# marquee-neopixel.net
KiCad netlist of a schematic drawn in EAGLE
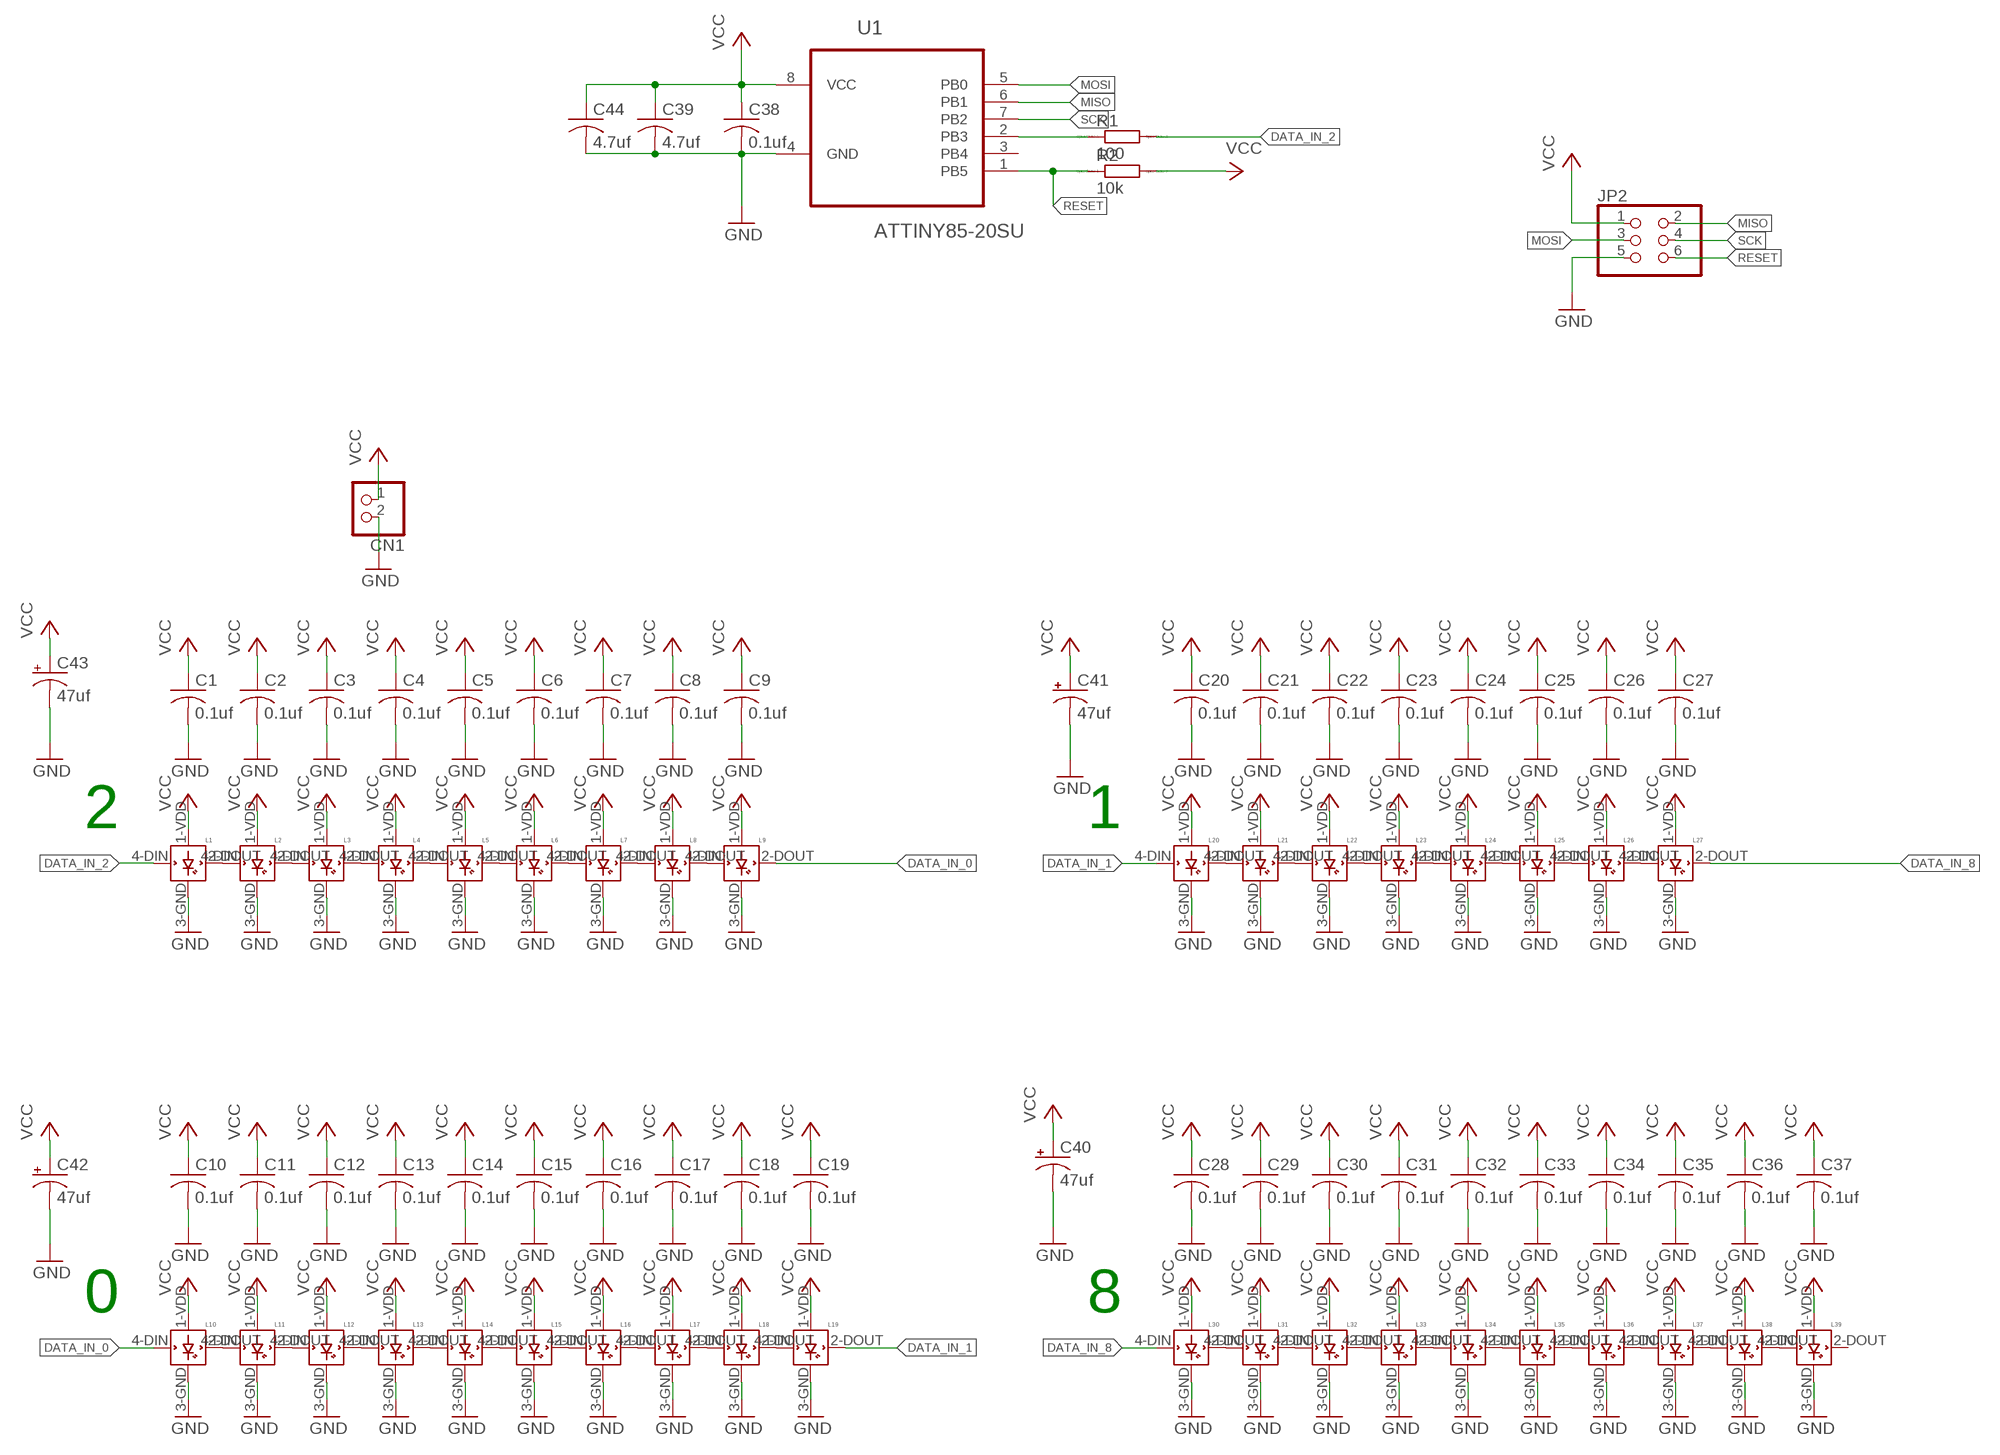
[diagram p0: schematic, sheet 1]

(export (version "E")
  (design (tool "Eeschema 10.0.6"))
  (components
    (comp (ref "C1")
      (value "0.1uf")
      (footprint "eagle-import:C0603")
      (libsource (lib "eagle-import") (part "C-USC0603"))
    )
    (comp (ref "C2")
      (value "0.1uf")
      (footprint "eagle-import:C0603")
      (libsource (lib "eagle-import") (part "C-USC0603"))
    )
    (comp (ref "C3")
      (value "0.1uf")
      (footprint "eagle-import:C0603")
      (libsource (lib "eagle-import") (part "C-USC0603"))
    )
    (comp (ref "C4")
      (value "0.1uf")
      (footprint "eagle-import:C0603")
      (libsource (lib "eagle-import") (part "C-USC0603"))
    )
    (comp (ref "C5")
      (value "0.1uf")
      (footprint "eagle-import:C0603")
      (libsource (lib "eagle-import") (part "C-USC0603"))
    )
    (comp (ref "C6")
      (value "0.1uf")
      (footprint "eagle-import:C0603")
      (libsource (lib "eagle-import") (part "C-USC0603"))
    )
    (comp (ref "C7")
      (value "0.1uf")
      (footprint "eagle-import:C0603")
      (libsource (lib "eagle-import") (part "C-USC0603"))
    )
    (comp (ref "C8")
      (value "0.1uf")
      (footprint "eagle-import:C0603")
      (libsource (lib "eagle-import") (part "C-USC0603"))
    )
    (comp (ref "C9")
      (value "0.1uf")
      (footprint "eagle-import:C0603")
      (libsource (lib "eagle-import") (part "C-USC0603"))
    )
    (comp (ref "C10")
      (value "0.1uf")
      (footprint "eagle-import:C0603")
      (libsource (lib "eagle-import") (part "C-USC0603"))
    )
    (comp (ref "C11")
      (value "0.1uf")
      (footprint "eagle-import:C0603")
      (libsource (lib "eagle-import") (part "C-USC0603"))
    )
    (comp (ref "C12")
      (value "0.1uf")
      (footprint "eagle-import:C0603")
      (libsource (lib "eagle-import") (part "C-USC0603"))
    )
    (comp (ref "C13")
      (value "0.1uf")
      (footprint "eagle-import:C0603")
      (libsource (lib "eagle-import") (part "C-USC0603"))
    )
    (comp (ref "C14")
      (value "0.1uf")
      (footprint "eagle-import:C0603")
      (libsource (lib "eagle-import") (part "C-USC0603"))
    )
    (comp (ref "C15")
      (value "0.1uf")
      (footprint "eagle-import:C0603")
      (libsource (lib "eagle-import") (part "C-USC0603"))
    )
    (comp (ref "C16")
      (value "0.1uf")
      (footprint "eagle-import:C0603")
      (libsource (lib "eagle-import") (part "C-USC0603"))
    )
    (comp (ref "C17")
      (value "0.1uf")
      (footprint "eagle-import:C0603")
      (libsource (lib "eagle-import") (part "C-USC0603"))
    )
    (comp (ref "C18")
      (value "0.1uf")
      (footprint "eagle-import:C0603")
      (libsource (lib "eagle-import") (part "C-USC0603"))
    )
    (comp (ref "C19")
      (value "0.1uf")
      (footprint "eagle-import:C0603")
      (libsource (lib "eagle-import") (part "C-USC0603"))
    )
    (comp (ref "C20")
      (value "0.1uf")
      (footprint "eagle-import:C0603")
      (libsource (lib "eagle-import") (part "C-USC0603"))
    )
    (comp (ref "C21")
      (value "0.1uf")
      (footprint "eagle-import:C0603")
      (libsource (lib "eagle-import") (part "C-USC0603"))
    )
    (comp (ref "C22")
      (value "0.1uf")
      (footprint "eagle-import:C0603")
      (libsource (lib "eagle-import") (part "C-USC0603"))
    )
    (comp (ref "C23")
      (value "0.1uf")
      (footprint "eagle-import:C0603")
      (libsource (lib "eagle-import") (part "C-USC0603"))
    )
    (comp (ref "C24")
      (value "0.1uf")
      (footprint "eagle-import:C0603")
      (libsource (lib "eagle-import") (part "C-USC0603"))
    )
    (comp (ref "C25")
      (value "0.1uf")
      (footprint "eagle-import:C0603")
      (libsource (lib "eagle-import") (part "C-USC0603"))
    )
    (comp (ref "C26")
      (value "0.1uf")
      (footprint "eagle-import:C0603")
      (libsource (lib "eagle-import") (part "C-USC0603"))
    )
    (comp (ref "C27")
      (value "0.1uf")
      (footprint "eagle-import:C0603")
      (libsource (lib "eagle-import") (part "C-USC0603"))
    )
    (comp (ref "C28")
      (value "0.1uf")
      (footprint "eagle-import:C0603")
      (libsource (lib "eagle-import") (part "C-USC0603"))
    )
    (comp (ref "C29")
      (value "0.1uf")
      (footprint "eagle-import:C0603")
      (libsource (lib "eagle-import") (part "C-USC0603"))
    )
    (comp (ref "C30")
      (value "0.1uf")
      (footprint "eagle-import:C0603")
      (libsource (lib "eagle-import") (part "C-USC0603"))
    )
    (comp (ref "C31")
      (value "0.1uf")
      (footprint "eagle-import:C0603")
      (libsource (lib "eagle-import") (part "C-USC0603"))
    )
    (comp (ref "C32")
      (value "0.1uf")
      (footprint "eagle-import:C0603")
      (libsource (lib "eagle-import") (part "C-USC0603"))
    )
    (comp (ref "C33")
      (value "0.1uf")
      (footprint "eagle-import:C0603")
      (libsource (lib "eagle-import") (part "C-USC0603"))
    )
    (comp (ref "C34")
      (value "0.1uf")
      (footprint "eagle-import:C0603")
      (libsource (lib "eagle-import") (part "C-USC0603"))
    )
    (comp (ref "C35")
      (value "0.1uf")
      (footprint "eagle-import:C0603")
      (libsource (lib "eagle-import") (part "C-USC0603"))
    )
    (comp (ref "C36")
      (value "0.1uf")
      (footprint "eagle-import:C0603")
      (libsource (lib "eagle-import") (part "C-USC0603"))
    )
    (comp (ref "C37")
      (value "0.1uf")
      (footprint "eagle-import:C0603")
      (libsource (lib "eagle-import") (part "C-USC0603"))
    )
    (comp (ref "C38")
      (value "0.1uf")
      (footprint "eagle-import:C0603")
      (libsource (lib "eagle-import") (part "C-USC0603"))
    )
    (comp (ref "C39")
      (value "4.7uf")
      (footprint "eagle-import:C0603")
      (libsource (lib "eagle-import") (part "C-USC0603"))
    )
    (comp (ref "C40")
      (value "47uf")
      (footprint "eagle-import:153CLV-0605")
      (libsource (lib "eagle-import") (part "CPOL-US153CLV-0605"))
    )
    (comp (ref "C41")
      (value "47uf")
      (footprint "eagle-import:153CLV-0605")
      (libsource (lib "eagle-import") (part "CPOL-US153CLV-0605"))
    )
    (comp (ref "C42")
      (value "47uf")
      (footprint "eagle-import:153CLV-0605")
      (libsource (lib "eagle-import") (part "CPOL-US153CLV-0605"))
    )
    (comp (ref "C43")
      (value "47uf")
      (footprint "eagle-import:153CLV-0605")
      (libsource (lib "eagle-import") (part "CPOL-US153CLV-0605"))
    )
    (comp (ref "C44")
      (value "4.7uf")
      (footprint "eagle-import:C0603")
      (libsource (lib "eagle-import") (part "C-USC0603"))
    )
    (comp (ref "CN1")
      (value "JST_2PIN-SMT-RA")
      (footprint "eagle-import:JST-PH-2-SMT-RA")
      (libsource (lib "eagle-import") (part "JST_2PIN-SMT-RA"))
    )
    (comp (ref "JP2")
      (value "PINHD-2X3")
      (footprint "eagle-import:2X03")
      (libsource (lib "eagle-import") (part "PINHD-2X3"))
    )
    (comp (ref "L1")
      (value "WS2812B")
      (footprint "eagle-import:WS2812B")
      (fields (field (name "SPICEPREFIX") "E"))
      (libsource (lib "eagle-import") (part "WS2812B"))
    )
    (comp (ref "L2")
      (value "WS2812B")
      (footprint "eagle-import:WS2812B")
      (fields (field (name "SPICEPREFIX") "E"))
      (libsource (lib "eagle-import") (part "WS2812B"))
    )
    (comp (ref "L3")
      (value "WS2812B")
      (footprint "eagle-import:WS2812B")
      (fields (field (name "SPICEPREFIX") "E"))
      (libsource (lib "eagle-import") (part "WS2812B"))
    )
    (comp (ref "L4")
      (value "WS2812B")
      (footprint "eagle-import:WS2812B")
      (fields (field (name "SPICEPREFIX") "E"))
      (libsource (lib "eagle-import") (part "WS2812B"))
    )
    (comp (ref "L5")
      (value "WS2812B")
      (footprint "eagle-import:WS2812B")
      (fields (field (name "SPICEPREFIX") "E"))
      (libsource (lib "eagle-import") (part "WS2812B"))
    )
    (comp (ref "L6")
      (value "WS2812B")
      (footprint "eagle-import:WS2812B")
      (fields (field (name "SPICEPREFIX") "E"))
      (libsource (lib "eagle-import") (part "WS2812B"))
    )
    (comp (ref "L7")
      (value "WS2812B")
      (footprint "eagle-import:WS2812B")
      (fields (field (name "SPICEPREFIX") "E"))
      (libsource (lib "eagle-import") (part "WS2812B"))
    )
    (comp (ref "L8")
      (value "WS2812B")
      (footprint "eagle-import:WS2812B")
      (fields (field (name "SPICEPREFIX") "E"))
      (libsource (lib "eagle-import") (part "WS2812B"))
    )
    (comp (ref "L9")
      (value "WS2812B")
      (footprint "eagle-import:WS2812B")
      (fields (field (name "SPICEPREFIX") "E"))
      (libsource (lib "eagle-import") (part "WS2812B"))
    )
    (comp (ref "L10")
      (value "WS2812B")
      (footprint "eagle-import:WS2812B")
      (libsource (lib "eagle-import") (part "WS2812B"))
    )
    (comp (ref "L11")
      (value "WS2812B")
      (footprint "eagle-import:WS2812B")
      (libsource (lib "eagle-import") (part "WS2812B"))
    )
    (comp (ref "L12")
      (value "WS2812B")
      (footprint "eagle-import:WS2812B")
      (libsource (lib "eagle-import") (part "WS2812B"))
    )
    (comp (ref "L13")
      (value "WS2812B")
      (footprint "eagle-import:WS2812B")
      (libsource (lib "eagle-import") (part "WS2812B"))
    )
    (comp (ref "L14")
      (value "WS2812B")
      (footprint "eagle-import:WS2812B")
      (libsource (lib "eagle-import") (part "WS2812B"))
    )
    (comp (ref "L15")
      (value "WS2812B")
      (footprint "eagle-import:WS2812B")
      (libsource (lib "eagle-import") (part "WS2812B"))
    )
    (comp (ref "L16")
      (value "WS2812B")
      (footprint "eagle-import:WS2812B")
      (libsource (lib "eagle-import") (part "WS2812B"))
    )
    (comp (ref "L17")
      (value "WS2812B")
      (footprint "eagle-import:WS2812B")
      (libsource (lib "eagle-import") (part "WS2812B"))
    )
    (comp (ref "L18")
      (value "WS2812B")
      (footprint "eagle-import:WS2812B")
      (libsource (lib "eagle-import") (part "WS2812B"))
    )
    (comp (ref "L19")
      (value "WS2812B")
      (footprint "eagle-import:WS2812B")
      (libsource (lib "eagle-import") (part "WS2812B"))
    )
    (comp (ref "L20")
      (value "WS2812B")
      (footprint "eagle-import:WS2812B")
      (libsource (lib "eagle-import") (part "WS2812B"))
    )
    (comp (ref "L21")
      (value "WS2812B")
      (footprint "eagle-import:WS2812B")
      (libsource (lib "eagle-import") (part "WS2812B"))
    )
    (comp (ref "L22")
      (value "WS2812B")
      (footprint "eagle-import:WS2812B")
      (libsource (lib "eagle-import") (part "WS2812B"))
    )
    (comp (ref "L23")
      (value "WS2812B")
      (footprint "eagle-import:WS2812B")
      (libsource (lib "eagle-import") (part "WS2812B"))
    )
    (comp (ref "L24")
      (value "WS2812B")
      (footprint "eagle-import:WS2812B")
      (libsource (lib "eagle-import") (part "WS2812B"))
    )
    (comp (ref "L25")
      (value "WS2812B")
      (footprint "eagle-import:WS2812B")
      (libsource (lib "eagle-import") (part "WS2812B"))
    )
    (comp (ref "L26")
      (value "WS2812B")
      (footprint "eagle-import:WS2812B")
      (libsource (lib "eagle-import") (part "WS2812B"))
    )
    (comp (ref "L27")
      (value "WS2812B")
      (footprint "eagle-import:WS2812B")
      (libsource (lib "eagle-import") (part "WS2812B"))
    )
    (comp (ref "L30")
      (value "WS2812B")
      (footprint "eagle-import:WS2812B")
      (libsource (lib "eagle-import") (part "WS2812B"))
    )
    (comp (ref "L31")
      (value "WS2812B")
      (footprint "eagle-import:WS2812B")
      (libsource (lib "eagle-import") (part "WS2812B"))
    )
    (comp (ref "L32")
      (value "WS2812B")
      (footprint "eagle-import:WS2812B")
      (libsource (lib "eagle-import") (part "WS2812B"))
    )
    (comp (ref "L33")
      (value "WS2812B")
      (footprint "eagle-import:WS2812B")
      (libsource (lib "eagle-import") (part "WS2812B"))
    )
    (comp (ref "L34")
      (value "WS2812B")
      (footprint "eagle-import:WS2812B")
      (libsource (lib "eagle-import") (part "WS2812B"))
    )
    (comp (ref "L35")
      (value "WS2812B")
      (footprint "eagle-import:WS2812B")
      (libsource (lib "eagle-import") (part "WS2812B"))
    )
    (comp (ref "L36")
      (value "WS2812B")
      (footprint "eagle-import:WS2812B")
      (libsource (lib "eagle-import") (part "WS2812B"))
    )
    (comp (ref "L37")
      (value "WS2812B")
      (footprint "eagle-import:WS2812B")
      (libsource (lib "eagle-import") (part "WS2812B"))
    )
    (comp (ref "L38")
      (value "WS2812B")
      (footprint "eagle-import:WS2812B")
      (libsource (lib "eagle-import") (part "WS2812B"))
    )
    (comp (ref "L39")
      (value "WS2812B")
      (footprint "eagle-import:WS2812B")
      (libsource (lib "eagle-import") (part "WS2812B"))
    )
    (comp (ref "R1")
      (value "100")
      (footprint "eagle-import:R0603")
      (libsource (lib "eagle-import") (part "RR0603"))
    )
    (comp (ref "R2")
      (value "10k")
      (footprint "eagle-import:R0603")
      (libsource (lib "eagle-import") (part "RR0603"))
    )
    (comp (ref "U1")
      (value "ATTINY85-20SU")
      (footprint "eagle-import:SOIC127P798X216-8N")
      (libsource (lib "eagle-import") (part "ATTINY85-20SU"))
    )
  )
  (nets
    (net (code "1") (name "DATA_IN_0") (class "Default")
      (node (ref "L10") (pin "4-DIN") (pinfunction "DIN_4-DIN") (pintype "input"))
      (node (ref "L9") (pin "2-DOUT") (pinfunction "DOUT_2-DOUT") (pintype "output"))
    )
    (net (code "2") (name "DATA_IN_1") (class "Default")
      (node (ref "L19") (pin "2-DOUT") (pinfunction "DOUT_2-DOUT") (pintype "output"))
      (node (ref "L20") (pin "4-DIN") (pinfunction "DIN_4-DIN") (pintype "input"))
    )
    (net (code "3") (name "DATA_IN_2") (class "Default")
      (node (ref "L1") (pin "4-DIN") (pinfunction "DIN_4-DIN") (pintype "input"))
      (node (ref "R1") (pin "2") (pinfunction "2_2") (pintype "passive"))
    )
    (net (code "4") (name "DATA_IN_8") (class "Default")
      (node (ref "L27") (pin "2-DOUT") (pinfunction "DOUT_2-DOUT") (pintype "output"))
      (node (ref "L30") (pin "4-DIN") (pinfunction "DIN_4-DIN") (pintype "input"))
    )
    (net (code "5") (name "GND") (class "Default")
      (node (ref "C1") (pin "2") (pinfunction "2_2") (pintype "passive"))
      (node (ref "C10") (pin "2") (pinfunction "2_2") (pintype "passive"))
      (node (ref "C11") (pin "2") (pinfunction "2_2") (pintype "passive"))
      (node (ref "C12") (pin "2") (pinfunction "2_2") (pintype "passive"))
      (node (ref "C13") (pin "2") (pinfunction "2_2") (pintype "passive"))
      (node (ref "C14") (pin "2") (pinfunction "2_2") (pintype "passive"))
      (node (ref "C15") (pin "2") (pinfunction "2_2") (pintype "passive"))
      (node (ref "C16") (pin "2") (pinfunction "2_2") (pintype "passive"))
      (node (ref "C17") (pin "2") (pinfunction "2_2") (pintype "passive"))
      (node (ref "C18") (pin "2") (pinfunction "2_2") (pintype "passive"))
      (node (ref "C19") (pin "2") (pinfunction "2_2") (pintype "passive"))
      (node (ref "C2") (pin "2") (pinfunction "2_2") (pintype "passive"))
      (node (ref "C20") (pin "2") (pinfunction "2_2") (pintype "passive"))
      (node (ref "C21") (pin "2") (pinfunction "2_2") (pintype "passive"))
      (node (ref "C22") (pin "2") (pinfunction "2_2") (pintype "passive"))
      (node (ref "C23") (pin "2") (pinfunction "2_2") (pintype "passive"))
      (node (ref "C24") (pin "2") (pinfunction "2_2") (pintype "passive"))
      (node (ref "C25") (pin "2") (pinfunction "2_2") (pintype "passive"))
      (node (ref "C26") (pin "2") (pinfunction "2_2") (pintype "passive"))
      (node (ref "C27") (pin "2") (pinfunction "2_2") (pintype "passive"))
      (node (ref "C28") (pin "2") (pinfunction "2_2") (pintype "passive"))
      (node (ref "C29") (pin "2") (pinfunction "2_2") (pintype "passive"))
      (node (ref "C3") (pin "2") (pinfunction "2_2") (pintype "passive"))
      (node (ref "C30") (pin "2") (pinfunction "2_2") (pintype "passive"))
      (node (ref "C31") (pin "2") (pinfunction "2_2") (pintype "passive"))
      (node (ref "C32") (pin "2") (pinfunction "2_2") (pintype "passive"))
      (node (ref "C33") (pin "2") (pinfunction "2_2") (pintype "passive"))
      (node (ref "C34") (pin "2") (pinfunction "2_2") (pintype "passive"))
      (node (ref "C35") (pin "2") (pinfunction "2_2") (pintype "passive"))
      (node (ref "C36") (pin "2") (pinfunction "2_2") (pintype "passive"))
      (node (ref "C37") (pin "2") (pinfunction "2_2") (pintype "passive"))
      (node (ref "C38") (pin "2") (pinfunction "2_2") (pintype "passive"))
      (node (ref "C39") (pin "2") (pinfunction "2_2") (pintype "passive"))
      (node (ref "C4") (pin "2") (pinfunction "2_2") (pintype "passive"))
      (node (ref "C40") (pin "-") (pinfunction "-_-") (pintype "passive"))
      (node (ref "C41") (pin "-") (pinfunction "-_-") (pintype "passive"))
      (node (ref "C42") (pin "-") (pinfunction "-_-") (pintype "passive"))
      (node (ref "C43") (pin "-") (pinfunction "-_-") (pintype "passive"))
      (node (ref "C44") (pin "2") (pinfunction "2_2") (pintype "passive"))
      (node (ref "C5") (pin "2") (pinfunction "2_2") (pintype "passive"))
      (node (ref "C6") (pin "2") (pinfunction "2_2") (pintype "passive"))
      (node (ref "C7") (pin "2") (pinfunction "2_2") (pintype "passive"))
      (node (ref "C8") (pin "2") (pinfunction "2_2") (pintype "passive"))
      (node (ref "C9") (pin "2") (pinfunction "2_2") (pintype "passive"))
      (node (ref "CN1") (pin "2") (pinfunction "1_2") (pintype "passive"))
      (node (ref "JP2") (pin "5") (pinfunction "5_5") (pintype "passive"))
      (node (ref "L1") (pin "3-GND") (pinfunction "GND_3-GND") (pintype "bidirectional"))
      (node (ref "L10") (pin "3-GND") (pinfunction "GND_3-GND") (pintype "bidirectional"))
      (node (ref "L11") (pin "3-GND") (pinfunction "GND_3-GND") (pintype "bidirectional"))
      (node (ref "L12") (pin "3-GND") (pinfunction "GND_3-GND") (pintype "bidirectional"))
      (node (ref "L13") (pin "3-GND") (pinfunction "GND_3-GND") (pintype "bidirectional"))
      (node (ref "L14") (pin "3-GND") (pinfunction "GND_3-GND") (pintype "bidirectional"))
      (node (ref "L15") (pin "3-GND") (pinfunction "GND_3-GND") (pintype "bidirectional"))
      (node (ref "L16") (pin "3-GND") (pinfunction "GND_3-GND") (pintype "bidirectional"))
      (node (ref "L17") (pin "3-GND") (pinfunction "GND_3-GND") (pintype "bidirectional"))
      (node (ref "L18") (pin "3-GND") (pinfunction "GND_3-GND") (pintype "bidirectional"))
      (node (ref "L19") (pin "3-GND") (pinfunction "GND_3-GND") (pintype "bidirectional"))
      (node (ref "L2") (pin "3-GND") (pinfunction "GND_3-GND") (pintype "bidirectional"))
      (node (ref "L20") (pin "3-GND") (pinfunction "GND_3-GND") (pintype "bidirectional"))
      (node (ref "L21") (pin "3-GND") (pinfunction "GND_3-GND") (pintype "bidirectional"))
      (node (ref "L22") (pin "3-GND") (pinfunction "GND_3-GND") (pintype "bidirectional"))
      (node (ref "L23") (pin "3-GND") (pinfunction "GND_3-GND") (pintype "bidirectional"))
      (node (ref "L24") (pin "3-GND") (pinfunction "GND_3-GND") (pintype "bidirectional"))
      (node (ref "L25") (pin "3-GND") (pinfunction "GND_3-GND") (pintype "bidirectional"))
      (node (ref "L26") (pin "3-GND") (pinfunction "GND_3-GND") (pintype "bidirectional"))
      (node (ref "L27") (pin "3-GND") (pinfunction "GND_3-GND") (pintype "bidirectional"))
      (node (ref "L3") (pin "3-GND") (pinfunction "GND_3-GND") (pintype "bidirectional"))
      (node (ref "L30") (pin "3-GND") (pinfunction "GND_3-GND") (pintype "bidirectional"))
      (node (ref "L31") (pin "3-GND") (pinfunction "GND_3-GND") (pintype "bidirectional"))
      (node (ref "L32") (pin "3-GND") (pinfunction "GND_3-GND") (pintype "bidirectional"))
      (node (ref "L33") (pin "3-GND") (pinfunction "GND_3-GND") (pintype "bidirectional"))
      (node (ref "L34") (pin "3-GND") (pinfunction "GND_3-GND") (pintype "bidirectional"))
      (node (ref "L35") (pin "3-GND") (pinfunction "GND_3-GND") (pintype "bidirectional"))
      (node (ref "L36") (pin "3-GND") (pinfunction "GND_3-GND") (pintype "bidirectional"))
      (node (ref "L37") (pin "3-GND") (pinfunction "GND_3-GND") (pintype "bidirectional"))
      (node (ref "L38") (pin "3-GND") (pinfunction "GND_3-GND") (pintype "bidirectional"))
      (node (ref "L39") (pin "3-GND") (pinfunction "GND_3-GND") (pintype "bidirectional"))
      (node (ref "L4") (pin "3-GND") (pinfunction "GND_3-GND") (pintype "bidirectional"))
      (node (ref "L5") (pin "3-GND") (pinfunction "GND_3-GND") (pintype "bidirectional"))
      (node (ref "L6") (pin "3-GND") (pinfunction "GND_3-GND") (pintype "bidirectional"))
      (node (ref "L7") (pin "3-GND") (pinfunction "GND_3-GND") (pintype "bidirectional"))
      (node (ref "L8") (pin "3-GND") (pinfunction "GND_3-GND") (pintype "bidirectional"))
      (node (ref "L9") (pin "3-GND") (pinfunction "GND_3-GND") (pintype "bidirectional"))
      (node (ref "U1") (pin "4") (pinfunction "GND_4") (pintype "passive"))
    )
    (net (code "6") (name "MISO") (class "Default")
      (node (ref "JP2") (pin "2") (pinfunction "2_2") (pintype "passive"))
      (node (ref "U1") (pin "6") (pinfunction "PB1_6") (pintype "bidirectional"))
    )
    (net (code "7") (name "MOSI") (class "Default")
      (node (ref "JP2") (pin "3") (pinfunction "3_3") (pintype "passive"))
      (node (ref "U1") (pin "5") (pinfunction "PB0_5") (pintype "bidirectional"))
    )
    (net (code "8") (name "Net-(L1-DOUT)") (class "Default")
      (node (ref "L1") (pin "2-DOUT") (pinfunction "DOUT_2-DOUT") (pintype "output"))
      (node (ref "L2") (pin "4-DIN") (pinfunction "DIN_4-DIN") (pintype "input"))
    )
    (net (code "9") (name "Net-(L2-DOUT)") (class "Default")
      (node (ref "L2") (pin "2-DOUT") (pinfunction "DOUT_2-DOUT") (pintype "output"))
      (node (ref "L3") (pin "4-DIN") (pinfunction "DIN_4-DIN") (pintype "input"))
    )
    (net (code "10") (name "Net-(L3-DOUT)") (class "Default")
      (node (ref "L3") (pin "2-DOUT") (pinfunction "DOUT_2-DOUT") (pintype "output"))
      (node (ref "L4") (pin "4-DIN") (pinfunction "DIN_4-DIN") (pintype "input"))
    )
    (net (code "11") (name "Net-(L4-DOUT)") (class "Default")
      (node (ref "L4") (pin "2-DOUT") (pinfunction "DOUT_2-DOUT") (pintype "output"))
      (node (ref "L5") (pin "4-DIN") (pinfunction "DIN_4-DIN") (pintype "input"))
    )
    (net (code "12") (name "Net-(L5-DOUT)") (class "Default")
      (node (ref "L5") (pin "2-DOUT") (pinfunction "DOUT_2-DOUT") (pintype "output"))
      (node (ref "L6") (pin "4-DIN") (pinfunction "DIN_4-DIN") (pintype "input"))
    )
    (net (code "13") (name "Net-(L6-DOUT)") (class "Default")
      (node (ref "L6") (pin "2-DOUT") (pinfunction "DOUT_2-DOUT") (pintype "output"))
      (node (ref "L7") (pin "4-DIN") (pinfunction "DIN_4-DIN") (pintype "input"))
    )
    (net (code "14") (name "Net-(L7-DOUT)") (class "Default")
      (node (ref "L7") (pin "2-DOUT") (pinfunction "DOUT_2-DOUT") (pintype "output"))
      (node (ref "L8") (pin "4-DIN") (pinfunction "DIN_4-DIN") (pintype "input"))
    )
    (net (code "15") (name "Net-(L8-DOUT)") (class "Default")
      (node (ref "L8") (pin "2-DOUT") (pinfunction "DOUT_2-DOUT") (pintype "output"))
      (node (ref "L9") (pin "4-DIN") (pinfunction "DIN_4-DIN") (pintype "input"))
    )
    (net (code "16") (name "Net-(L10-DOUT)") (class "Default")
      (node (ref "L10") (pin "2-DOUT") (pinfunction "DOUT_2-DOUT") (pintype "output"))
      (node (ref "L11") (pin "4-DIN") (pinfunction "DIN_4-DIN") (pintype "input"))
    )
    (net (code "17") (name "Net-(L11-DOUT)") (class "Default")
      (node (ref "L11") (pin "2-DOUT") (pinfunction "DOUT_2-DOUT") (pintype "output"))
      (node (ref "L12") (pin "4-DIN") (pinfunction "DIN_4-DIN") (pintype "input"))
    )
    (net (code "18") (name "Net-(L12-DOUT)") (class "Default")
      (node (ref "L12") (pin "2-DOUT") (pinfunction "DOUT_2-DOUT") (pintype "output"))
      (node (ref "L13") (pin "4-DIN") (pinfunction "DIN_4-DIN") (pintype "input"))
    )
    (net (code "19") (name "Net-(L13-DOUT)") (class "Default")
      (node (ref "L13") (pin "2-DOUT") (pinfunction "DOUT_2-DOUT") (pintype "output"))
      (node (ref "L14") (pin "4-DIN") (pinfunction "DIN_4-DIN") (pintype "input"))
    )
    (net (code "20") (name "Net-(L14-DOUT)") (class "Default")
      (node (ref "L14") (pin "2-DOUT") (pinfunction "DOUT_2-DOUT") (pintype "output"))
      (node (ref "L15") (pin "4-DIN") (pinfunction "DIN_4-DIN") (pintype "input"))
    )
    (net (code "21") (name "Net-(L15-DOUT)") (class "Default")
      (node (ref "L15") (pin "2-DOUT") (pinfunction "DOUT_2-DOUT") (pintype "output"))
      (node (ref "L16") (pin "4-DIN") (pinfunction "DIN_4-DIN") (pintype "input"))
    )
    (net (code "22") (name "Net-(L16-DOUT)") (class "Default")
      (node (ref "L16") (pin "2-DOUT") (pinfunction "DOUT_2-DOUT") (pintype "output"))
      (node (ref "L17") (pin "4-DIN") (pinfunction "DIN_4-DIN") (pintype "input"))
    )
    (net (code "23") (name "Net-(L17-DOUT)") (class "Default")
      (node (ref "L17") (pin "2-DOUT") (pinfunction "DOUT_2-DOUT") (pintype "output"))
      (node (ref "L18") (pin "4-DIN") (pinfunction "DIN_4-DIN") (pintype "input"))
    )
    (net (code "24") (name "Net-(L18-DOUT)") (class "Default")
      (node (ref "L18") (pin "2-DOUT") (pinfunction "DOUT_2-DOUT") (pintype "output"))
      (node (ref "L19") (pin "4-DIN") (pinfunction "DIN_4-DIN") (pintype "input"))
    )
    (net (code "25") (name "Net-(L20-DOUT)") (class "Default")
      (node (ref "L20") (pin "2-DOUT") (pinfunction "DOUT_2-DOUT") (pintype "output"))
      (node (ref "L21") (pin "4-DIN") (pinfunction "DIN_4-DIN") (pintype "input"))
    )
    (net (code "26") (name "Net-(L21-DOUT)") (class "Default")
      (node (ref "L21") (pin "2-DOUT") (pinfunction "DOUT_2-DOUT") (pintype "output"))
      (node (ref "L22") (pin "4-DIN") (pinfunction "DIN_4-DIN") (pintype "input"))
    )
    (net (code "27") (name "Net-(L22-DOUT)") (class "Default")
      (node (ref "L22") (pin "2-DOUT") (pinfunction "DOUT_2-DOUT") (pintype "output"))
      (node (ref "L23") (pin "4-DIN") (pinfunction "DIN_4-DIN") (pintype "input"))
    )
    (net (code "28") (name "Net-(L23-DOUT)") (class "Default")
      (node (ref "L23") (pin "2-DOUT") (pinfunction "DOUT_2-DOUT") (pintype "output"))
      (node (ref "L24") (pin "4-DIN") (pinfunction "DIN_4-DIN") (pintype "input"))
    )
    (net (code "29") (name "Net-(L24-DOUT)") (class "Default")
      (node (ref "L24") (pin "2-DOUT") (pinfunction "DOUT_2-DOUT") (pintype "output"))
      (node (ref "L25") (pin "4-DIN") (pinfunction "DIN_4-DIN") (pintype "input"))
    )
    (net (code "30") (name "Net-(L25-DOUT)") (class "Default")
      (node (ref "L25") (pin "2-DOUT") (pinfunction "DOUT_2-DOUT") (pintype "output"))
      (node (ref "L26") (pin "4-DIN") (pinfunction "DIN_4-DIN") (pintype "input"))
    )
    (net (code "31") (name "Net-(L26-DOUT)") (class "Default")
      (node (ref "L26") (pin "2-DOUT") (pinfunction "DOUT_2-DOUT") (pintype "output"))
      (node (ref "L27") (pin "4-DIN") (pinfunction "DIN_4-DIN") (pintype "input"))
    )
    (net (code "32") (name "Net-(L30-DOUT)") (class "Default")
      (node (ref "L30") (pin "2-DOUT") (pinfunction "DOUT_2-DOUT") (pintype "output"))
      (node (ref "L31") (pin "4-DIN") (pinfunction "DIN_4-DIN") (pintype "input"))
    )
    (net (code "33") (name "Net-(L31-DOUT)") (class "Default")
      (node (ref "L31") (pin "2-DOUT") (pinfunction "DOUT_2-DOUT") (pintype "output"))
      (node (ref "L32") (pin "4-DIN") (pinfunction "DIN_4-DIN") (pintype "input"))
    )
    (net (code "34") (name "Net-(L32-DOUT)") (class "Default")
      (node (ref "L32") (pin "2-DOUT") (pinfunction "DOUT_2-DOUT") (pintype "output"))
      (node (ref "L33") (pin "4-DIN") (pinfunction "DIN_4-DIN") (pintype "input"))
    )
    (net (code "35") (name "Net-(L33-DOUT)") (class "Default")
      (node (ref "L33") (pin "2-DOUT") (pinfunction "DOUT_2-DOUT") (pintype "output"))
      (node (ref "L34") (pin "4-DIN") (pinfunction "DIN_4-DIN") (pintype "input"))
    )
    (net (code "36") (name "Net-(L34-DOUT)") (class "Default")
      (node (ref "L34") (pin "2-DOUT") (pinfunction "DOUT_2-DOUT") (pintype "output"))
      (node (ref "L35") (pin "4-DIN") (pinfunction "DIN_4-DIN") (pintype "input"))
    )
    (net (code "37") (name "Net-(L35-DOUT)") (class "Default")
      (node (ref "L35") (pin "2-DOUT") (pinfunction "DOUT_2-DOUT") (pintype "output"))
      (node (ref "L36") (pin "4-DIN") (pinfunction "DIN_4-DIN") (pintype "input"))
    )
    (net (code "38") (name "Net-(L36-DOUT)") (class "Default")
      (node (ref "L36") (pin "2-DOUT") (pinfunction "DOUT_2-DOUT") (pintype "output"))
      (node (ref "L37") (pin "4-DIN") (pinfunction "DIN_4-DIN") (pintype "input"))
    )
    (net (code "39") (name "Net-(L37-DOUT)") (class "Default")
      (node (ref "L37") (pin "2-DOUT") (pinfunction "DOUT_2-DOUT") (pintype "output"))
      (node (ref "L38") (pin "4-DIN") (pinfunction "DIN_4-DIN") (pintype "input"))
    )
    (net (code "40") (name "Net-(L38-DOUT)") (class "Default")
      (node (ref "L38") (pin "2-DOUT") (pinfunction "DOUT_2-DOUT") (pintype "output"))
      (node (ref "L39") (pin "4-DIN") (pinfunction "DIN_4-DIN") (pintype "input"))
    )
    (net (code "41") (name "Net-(U1-PB3)") (class "Default")
      (node (ref "R1") (pin "1") (pinfunction "1_1") (pintype "passive"))
      (node (ref "U1") (pin "2") (pinfunction "PB3_2") (pintype "bidirectional"))
    )
    (net (code "42") (name "RESET") (class "Default")
      (node (ref "JP2") (pin "6") (pinfunction "6_6") (pintype "passive"))
      (node (ref "R2") (pin "1") (pinfunction "1_1") (pintype "passive"))
      (node (ref "U1") (pin "1") (pinfunction "PB5_1") (pintype "bidirectional"))
    )
    (net (code "43") (name "SCK") (class "Default")
      (node (ref "JP2") (pin "4") (pinfunction "4_4") (pintype "passive"))
      (node (ref "U1") (pin "7") (pinfunction "PB2_7") (pintype "bidirectional"))
    )
    (net (code "44") (name "VCC") (class "Default")
      (node (ref "C1") (pin "1") (pinfunction "1_1") (pintype "passive"))
      (node (ref "C10") (pin "1") (pinfunction "1_1") (pintype "passive"))
      (node (ref "C11") (pin "1") (pinfunction "1_1") (pintype "passive"))
      (node (ref "C12") (pin "1") (pinfunction "1_1") (pintype "passive"))
      (node (ref "C13") (pin "1") (pinfunction "1_1") (pintype "passive"))
      (node (ref "C14") (pin "1") (pinfunction "1_1") (pintype "passive"))
      (node (ref "C15") (pin "1") (pinfunction "1_1") (pintype "passive"))
      (node (ref "C16") (pin "1") (pinfunction "1_1") (pintype "passive"))
      (node (ref "C17") (pin "1") (pinfunction "1_1") (pintype "passive"))
      (node (ref "C18") (pin "1") (pinfunction "1_1") (pintype "passive"))
      (node (ref "C19") (pin "1") (pinfunction "1_1") (pintype "passive"))
      (node (ref "C2") (pin "1") (pinfunction "1_1") (pintype "passive"))
      (node (ref "C20") (pin "1") (pinfunction "1_1") (pintype "passive"))
      (node (ref "C21") (pin "1") (pinfunction "1_1") (pintype "passive"))
      (node (ref "C22") (pin "1") (pinfunction "1_1") (pintype "passive"))
      (node (ref "C23") (pin "1") (pinfunction "1_1") (pintype "passive"))
      (node (ref "C24") (pin "1") (pinfunction "1_1") (pintype "passive"))
      (node (ref "C25") (pin "1") (pinfunction "1_1") (pintype "passive"))
      (node (ref "C26") (pin "1") (pinfunction "1_1") (pintype "passive"))
      (node (ref "C27") (pin "1") (pinfunction "1_1") (pintype "passive"))
      (node (ref "C28") (pin "1") (pinfunction "1_1") (pintype "passive"))
      (node (ref "C29") (pin "1") (pinfunction "1_1") (pintype "passive"))
      (node (ref "C3") (pin "1") (pinfunction "1_1") (pintype "passive"))
      (node (ref "C30") (pin "1") (pinfunction "1_1") (pintype "passive"))
      (node (ref "C31") (pin "1") (pinfunction "1_1") (pintype "passive"))
      (node (ref "C32") (pin "1") (pinfunction "1_1") (pintype "passive"))
      (node (ref "C33") (pin "1") (pinfunction "1_1") (pintype "passive"))
      (node (ref "C34") (pin "1") (pinfunction "1_1") (pintype "passive"))
      (node (ref "C35") (pin "1") (pinfunction "1_1") (pintype "passive"))
      (node (ref "C36") (pin "1") (pinfunction "1_1") (pintype "passive"))
      (node (ref "C37") (pin "1") (pinfunction "1_1") (pintype "passive"))
      (node (ref "C38") (pin "1") (pinfunction "1_1") (pintype "passive"))
      (node (ref "C39") (pin "1") (pinfunction "1_1") (pintype "passive"))
      (node (ref "C4") (pin "1") (pinfunction "1_1") (pintype "passive"))
      (node (ref "C40") (pin "+") (pinfunction "+_+") (pintype "passive"))
      (node (ref "C41") (pin "+") (pinfunction "+_+") (pintype "passive"))
      (node (ref "C42") (pin "+") (pinfunction "+_+") (pintype "passive"))
      (node (ref "C43") (pin "+") (pinfunction "+_+") (pintype "passive"))
      (node (ref "C44") (pin "1") (pinfunction "1_1") (pintype "passive"))
      (node (ref "C5") (pin "1") (pinfunction "1_1") (pintype "passive"))
      (node (ref "C6") (pin "1") (pinfunction "1_1") (pintype "passive"))
      (node (ref "C7") (pin "1") (pinfunction "1_1") (pintype "passive"))
      (node (ref "C8") (pin "1") (pinfunction "1_1") (pintype "passive"))
      (node (ref "C9") (pin "1") (pinfunction "1_1") (pintype "passive"))
      (node (ref "CN1") (pin "1") (pinfunction "2_1") (pintype "passive"))
      (node (ref "JP2") (pin "1") (pinfunction "1_1") (pintype "passive"))
      (node (ref "L1") (pin "1-VDD") (pinfunction "VDD_1-VDD") (pintype "bidirectional"))
      (node (ref "L10") (pin "1-VDD") (pinfunction "VDD_1-VDD") (pintype "bidirectional"))
      (node (ref "L11") (pin "1-VDD") (pinfunction "VDD_1-VDD") (pintype "bidirectional"))
      (node (ref "L12") (pin "1-VDD") (pinfunction "VDD_1-VDD") (pintype "bidirectional"))
      (node (ref "L13") (pin "1-VDD") (pinfunction "VDD_1-VDD") (pintype "bidirectional"))
      (node (ref "L14") (pin "1-VDD") (pinfunction "VDD_1-VDD") (pintype "bidirectional"))
      (node (ref "L15") (pin "1-VDD") (pinfunction "VDD_1-VDD") (pintype "bidirectional"))
      (node (ref "L16") (pin "1-VDD") (pinfunction "VDD_1-VDD") (pintype "bidirectional"))
      (node (ref "L17") (pin "1-VDD") (pinfunction "VDD_1-VDD") (pintype "bidirectional"))
      (node (ref "L18") (pin "1-VDD") (pinfunction "VDD_1-VDD") (pintype "bidirectional"))
      (node (ref "L19") (pin "1-VDD") (pinfunction "VDD_1-VDD") (pintype "bidirectional"))
      (node (ref "L2") (pin "1-VDD") (pinfunction "VDD_1-VDD") (pintype "bidirectional"))
      (node (ref "L20") (pin "1-VDD") (pinfunction "VDD_1-VDD") (pintype "bidirectional"))
      (node (ref "L21") (pin "1-VDD") (pinfunction "VDD_1-VDD") (pintype "bidirectional"))
      (node (ref "L22") (pin "1-VDD") (pinfunction "VDD_1-VDD") (pintype "bidirectional"))
      (node (ref "L23") (pin "1-VDD") (pinfunction "VDD_1-VDD") (pintype "bidirectional"))
      (node (ref "L24") (pin "1-VDD") (pinfunction "VDD_1-VDD") (pintype "bidirectional"))
      (node (ref "L25") (pin "1-VDD") (pinfunction "VDD_1-VDD") (pintype "bidirectional"))
      (node (ref "L26") (pin "1-VDD") (pinfunction "VDD_1-VDD") (pintype "bidirectional"))
      (node (ref "L27") (pin "1-VDD") (pinfunction "VDD_1-VDD") (pintype "bidirectional"))
      (node (ref "L3") (pin "1-VDD") (pinfunction "VDD_1-VDD") (pintype "bidirectional"))
      (node (ref "L30") (pin "1-VDD") (pinfunction "VDD_1-VDD") (pintype "bidirectional"))
      (node (ref "L31") (pin "1-VDD") (pinfunction "VDD_1-VDD") (pintype "bidirectional"))
      (node (ref "L32") (pin "1-VDD") (pinfunction "VDD_1-VDD") (pintype "bidirectional"))
      (node (ref "L33") (pin "1-VDD") (pinfunction "VDD_1-VDD") (pintype "bidirectional"))
      (node (ref "L34") (pin "1-VDD") (pinfunction "VDD_1-VDD") (pintype "bidirectional"))
      (node (ref "L35") (pin "1-VDD") (pinfunction "VDD_1-VDD") (pintype "bidirectional"))
      (node (ref "L36") (pin "1-VDD") (pinfunction "VDD_1-VDD") (pintype "bidirectional"))
      (node (ref "L37") (pin "1-VDD") (pinfunction "VDD_1-VDD") (pintype "bidirectional"))
      (node (ref "L38") (pin "1-VDD") (pinfunction "VDD_1-VDD") (pintype "bidirectional"))
      (node (ref "L39") (pin "1-VDD") (pinfunction "VDD_1-VDD") (pintype "bidirectional"))
      (node (ref "L4") (pin "1-VDD") (pinfunction "VDD_1-VDD") (pintype "bidirectional"))
      (node (ref "L5") (pin "1-VDD") (pinfunction "VDD_1-VDD") (pintype "bidirectional"))
      (node (ref "L6") (pin "1-VDD") (pinfunction "VDD_1-VDD") (pintype "bidirectional"))
      (node (ref "L7") (pin "1-VDD") (pinfunction "VDD_1-VDD") (pintype "bidirectional"))
      (node (ref "L8") (pin "1-VDD") (pinfunction "VDD_1-VDD") (pintype "bidirectional"))
      (node (ref "L9") (pin "1-VDD") (pinfunction "VDD_1-VDD") (pintype "bidirectional"))
      (node (ref "R2") (pin "2") (pinfunction "2_2") (pintype "passive"))
      (node (ref "U1") (pin "8") (pinfunction "VCC_8") (pintype "power_in"))
    )
    (net (code "45") (name "unconnected-(L39-DOUT-Pad2-DOUT)") (class "Default")
      (node (ref "L39") (pin "2-DOUT") (pinfunction "DOUT_2-DOUT") (pintype "output"))
    )
    (net (code "46") (name "unconnected-(U1-PB4-Pad3)") (class "Default")
      (node (ref "U1") (pin "3") (pinfunction "PB4_3") (pintype "bidirectional"))
    )
  )
)
